# Usb_SdCard.net
KiCad netlist of a schematic drawn in Altium Designer
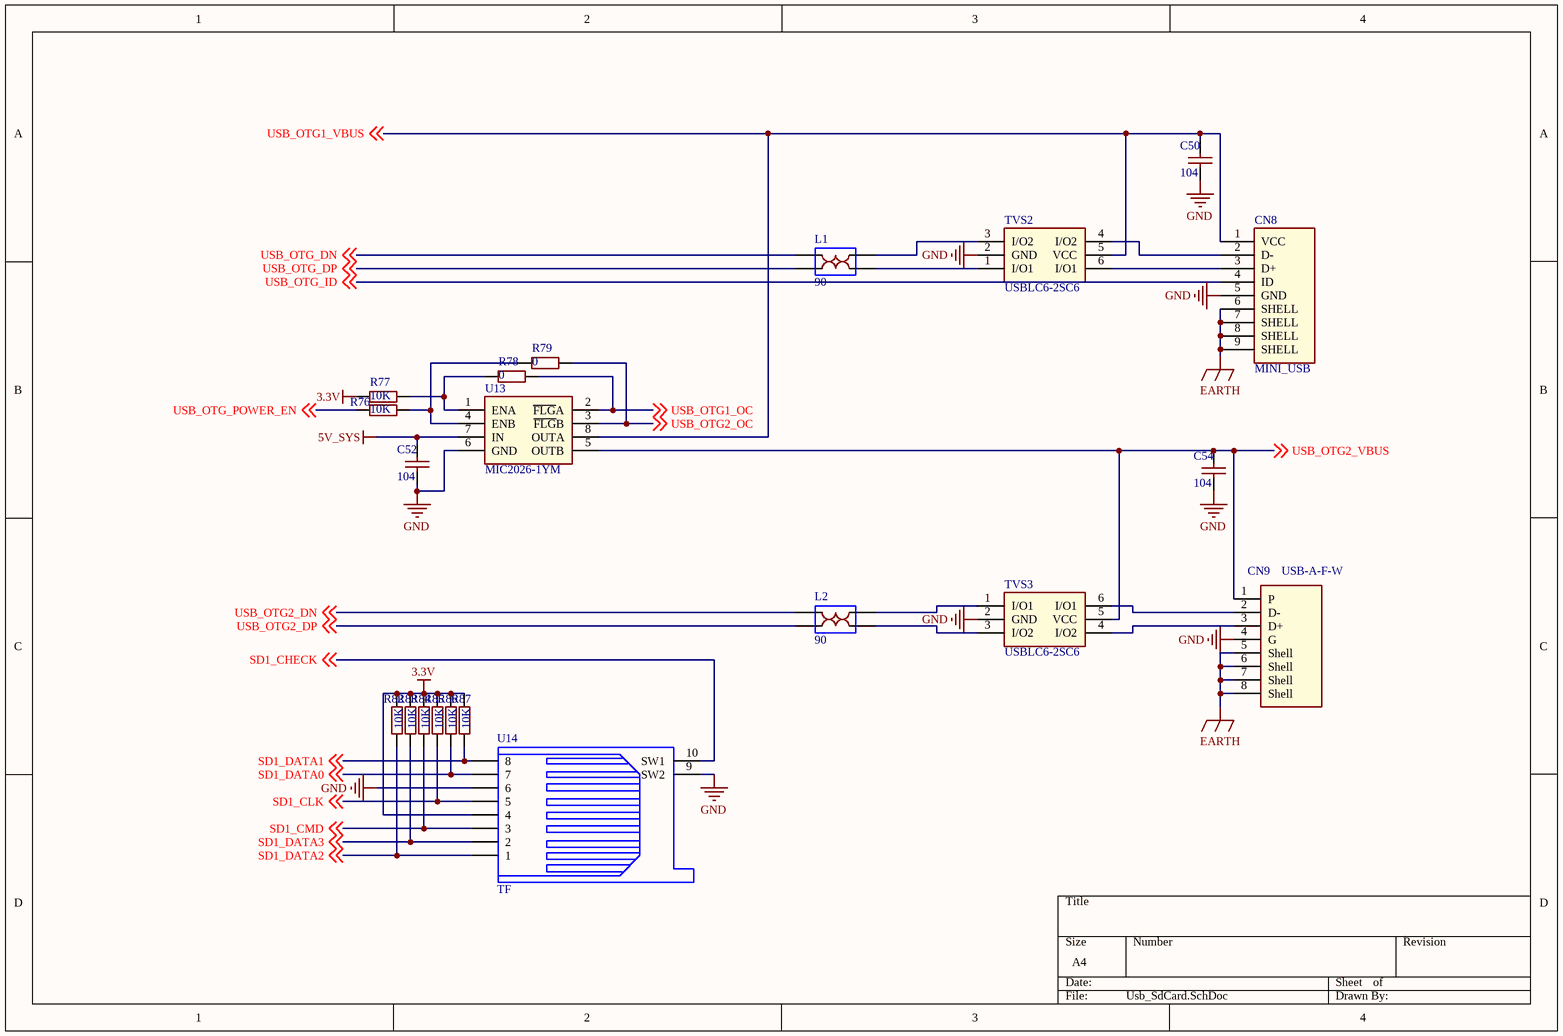
[diagram p0: Usb_SdCard.SchDoc]

(export (version "E")
  (design (tool "Eeschema 10.0.6"))
  (components
    (comp (ref "C50")
      (value "104")
      (footprint "0805SMD_Cap")
      (description "贴片电容")
      (libsource (lib "ST_GND_Sch") (part "SMD_Cap"))
    )
    (comp (ref "C52")
      (value "104")
      (footprint "0805SMD_Cap")
      (description "贴片电容")
      (libsource (lib "ST_GND_Sch") (part "SMD_Cap"))
    )
    (comp (ref "C54")
      (value "104")
      (footprint "0805SMD_Cap")
      (description "贴片电容")
      (libsource (lib "ST_GND_Sch") (part "SMD_Cap"))
    )
    (comp (ref "CN8")
      (value "MINI_USB")
      (footprint "MICRO_USB")
      (libsource (lib "ST_GND_Sch") (part "MINI_USB"))
    )
    (comp (ref "CN9")
      (value "USB-A-F-W")
      (footprint "USB-C")
      (libsource (lib "ST_GND_Sch") (part "USB-A-F-W"))
    )
    (comp (ref "L1") (value "90") (footprint "2012") (libsource (lib "") (part "共模电感_1")))
    (comp (ref "L2") (value "90") (footprint "2012") (libsource (lib "ST_GND_Sch") (part "共模电感")))
    (comp (ref "R76")
      (value "10K")
      (footprint "0805_SMD_R")
      (description "贴片电阻")
      (libsource (lib "") (part "SMD_0805_1"))
    )
    (comp (ref "R77")
      (value "10K")
      (footprint "0805_SMD_R")
      (description "贴片电阻")
      (libsource (lib "") (part "SMD_0805_1"))
    )
    (comp (ref "R78")
      (value "0")
      (footprint "0805_SMD_R")
      (description "贴片电阻")
      (libsource (lib "") (part "SMD_0805_1"))
    )
    (comp (ref "R79")
      (value "0")
      (footprint "0805_SMD_R")
      (description "贴片电阻")
      (libsource (lib "") (part "SMD_0805_1"))
    )
    (comp (ref "R82")
      (value "10K")
      (footprint "0805_SMD_R")
      (description "贴片电阻")
      (libsource (lib "ST_GND_Sch") (part "SMD_0805"))
    )
    (comp (ref "R83")
      (value "10K")
      (footprint "0805_SMD_R")
      (description "贴片电阻")
      (libsource (lib "ST_GND_Sch") (part "SMD_0805"))
    )
    (comp (ref "R84")
      (value "10K")
      (footprint "0805_SMD_R")
      (description "贴片电阻")
      (libsource (lib "ST_GND_Sch") (part "SMD_0805"))
    )
    (comp (ref "R85")
      (value "10K")
      (footprint "0805_SMD_R")
      (description "贴片电阻")
      (libsource (lib "ST_GND_Sch") (part "SMD_0805"))
    )
    (comp (ref "R86")
      (value "10K")
      (footprint "0805_SMD_R")
      (description "贴片电阻")
      (libsource (lib "ST_GND_Sch") (part "SMD_0805"))
    )
    (comp (ref "R87")
      (value "10K")
      (footprint "0805_SMD_R")
      (description "贴片电阻")
      (libsource (lib "ST_GND_Sch") (part "SMD_0805"))
    )
    (comp (ref "TVS2")
      (value "USBLC6-2SC6")
      (footprint "SOT-23-6")
      (libsource (lib "") (part "USBLC6-2SC6_1"))
    )
    (comp (ref "TVS3")
      (value "USBLC6-2SC6")
      (footprint "SOT-23-6")
      (libsource (lib "ST_GND_Sch") (part "USBLC6-2SC6"))
    )
    (comp (ref "U13")
      (value "MIC2026-1YM")
      (footprint "运放SO8")
      (libsource (lib "ST_GND_Sch") (part "MIC2026-1YM"))
    )
    (comp (ref "U14") (value "TF") (footprint "TF") (libsource (lib "ST_GND_Sch") (part "TF")))
  )
  (nets
    (net (code "1") (name "3.3V") (class "Default")
      (node (ref "R77") (pin "2") (pinfunction "2_2") (pintype "passive"))
      (node (ref "R82") (pin "2") (pinfunction "2_2") (pintype "passive"))
      (node (ref "R83") (pin "2") (pinfunction "2_2") (pintype "passive"))
      (node (ref "R84") (pin "2") (pinfunction "2_2") (pintype "passive"))
      (node (ref "R85") (pin "2") (pinfunction "2_2") (pintype "passive"))
      (node (ref "R86") (pin "2") (pinfunction "2_2") (pintype "passive"))
      (node (ref "R87") (pin "2") (pinfunction "2_2") (pintype "passive"))
      (node (ref "U14") (pin "4") (pinfunction "4_4") (pintype "passive"))
    )
    (net (code "2") (name "5V_SYS") (class "Default")
      (node (ref "C52") (pin "1") (pintype "passive"))
      (node (ref "U13") (pin "7") (pinfunction "IN_7") (pintype "passive"))
    )
    (net (code "3") (name "EARTH") (class "Default")
      (node (ref "CN8") (pin "6") (pinfunction "SHELL_6") (pintype "passive"))
      (node (ref "CN8") (pin "7") (pinfunction "SHELL_7") (pintype "passive"))
      (node (ref "CN8") (pin "8") (pinfunction "SHELL_8") (pintype "passive"))
      (node (ref "CN8") (pin "9") (pinfunction "SHELL_9") (pintype "passive"))
      (node (ref "CN9") (pin "5") (pinfunction "Shell_5") (pintype "passive"))
      (node (ref "CN9") (pin "6") (pinfunction "Shell_6") (pintype "passive"))
      (node (ref "CN9") (pin "7") (pinfunction "Shell_7") (pintype "power_in"))
      (node (ref "CN9") (pin "8") (pinfunction "Shell_8") (pintype "power_in"))
    )
    (net (code "4") (name "GND") (class "Default")
      (node (ref "C50") (pin "2") (pintype "passive"))
      (node (ref "C52") (pin "2") (pintype "passive"))
      (node (ref "C54") (pin "2") (pintype "passive"))
      (node (ref "CN8") (pin "5") (pinfunction "GND_5") (pintype "power_in"))
      (node (ref "CN9") (pin "4") (pinfunction "G_4") (pintype "passive"))
      (node (ref "TVS2") (pin "2") (pinfunction "GND_2") (pintype "passive"))
      (node (ref "TVS3") (pin "2") (pinfunction "GND_2") (pintype "passive"))
      (node (ref "U13") (pin "6") (pinfunction "GND_6") (pintype "passive"))
      (node (ref "U14") (pin "6") (pinfunction "6_6") (pintype "passive"))
      (node (ref "U14") (pin "9") (pinfunction "SW2_9") (pintype "passive"))
    )
    (net (code "5") (name "Net-(CN8-D+)") (class "Default")
      (node (ref "CN8") (pin "3") (pinfunction "D+_3") (pintype "passive"))
      (node (ref "TVS2") (pin "6") (pinfunction "I/O1_6") (pintype "passive"))
    )
    (net (code "6") (name "Net-(CN8-D-)") (class "Default")
      (node (ref "CN8") (pin "2") (pinfunction "D-_2") (pintype "passive"))
      (node (ref "TVS2") (pin "4") (pinfunction "I/O2_4") (pintype "passive"))
    )
    (net (code "7") (name "Net-(CN9-D+)") (class "Default")
      (node (ref "CN9") (pin "3") (pinfunction "D+_3") (pintype "passive"))
      (node (ref "TVS3") (pin "4") (pinfunction "I/O2_4") (pintype "passive"))
    )
    (net (code "8") (name "Net-(CN9-D-)") (class "Default")
      (node (ref "CN9") (pin "2") (pinfunction "D-_2") (pintype "passive"))
      (node (ref "TVS3") (pin "6") (pinfunction "I/O1_6") (pintype "passive"))
    )
    (net (code "9") (name "Net-(L1-Pad3)") (class "Default")
      (node (ref "L1") (pin "3") (pinfunction "3_3") (pintype "passive"))
      (node (ref "TVS2") (pin "3") (pinfunction "I/O2_3") (pintype "passive"))
    )
    (net (code "10") (name "Net-(L1-Pad4)") (class "Default")
      (node (ref "L1") (pin "4") (pinfunction "4_4") (pintype "passive"))
      (node (ref "TVS2") (pin "1") (pinfunction "I/O1_1") (pintype "passive"))
    )
    (net (code "11") (name "Net-(L2-Pad3)") (class "Default")
      (node (ref "L2") (pin "3") (pinfunction "3_3") (pintype "passive"))
      (node (ref "TVS3") (pin "3") (pinfunction "I/O2_3") (pintype "passive"))
    )
    (net (code "12") (name "Net-(L2-Pad4)") (class "Default")
      (node (ref "L2") (pin "4") (pinfunction "4_4") (pintype "passive"))
      (node (ref "TVS3") (pin "1") (pinfunction "I/O1_1") (pintype "passive"))
    )
    (net (code "13") (name "Net-(U13-ENA)") (class "Default")
      (node (ref "R77") (pin "1") (pinfunction "1_1") (pintype "passive"))
      (node (ref "R78") (pin "2") (pinfunction "2_2") (pintype "passive"))
      (node (ref "U13") (pin "1") (pinfunction "ENA_1") (pintype "passive"))
    )
    (net (code "14") (name "Net-(U13-ENB)") (class "Default")
      (node (ref "R76") (pin "1") (pinfunction "1_1") (pintype "passive"))
      (node (ref "R79") (pin "2") (pinfunction "2_2") (pintype "passive"))
      (node (ref "U13") (pin "4") (pinfunction "ENB_4") (pintype "passive"))
    )
    (net (code "15") (name "SD1_CHECK") (class "Default")
      (node (ref "U14") (pin "10") (pinfunction "SW1_10") (pintype "passive"))
    )
    (net (code "16") (name "SD1_CLK") (class "Default")
      (node (ref "R85") (pin "1") (pinfunction "1_1") (pintype "passive"))
      (node (ref "U14") (pin "5") (pinfunction "5_5") (pintype "passive"))
    )
    (net (code "17") (name "SD1_CMD") (class "Default")
      (node (ref "R84") (pin "1") (pinfunction "1_1") (pintype "passive"))
      (node (ref "U14") (pin "3") (pinfunction "3_3") (pintype "passive"))
    )
    (net (code "18") (name "SD1_DATA0") (class "Default")
      (node (ref "R86") (pin "1") (pinfunction "1_1") (pintype "passive"))
      (node (ref "U14") (pin "7") (pinfunction "7_7") (pintype "passive"))
    )
    (net (code "19") (name "SD1_DATA1") (class "Default")
      (node (ref "R87") (pin "1") (pinfunction "1_1") (pintype "passive"))
      (node (ref "U14") (pin "8") (pinfunction "8_8") (pintype "passive"))
    )
    (net (code "20") (name "SD1_DATA2") (class "Default")
      (node (ref "R82") (pin "1") (pinfunction "1_1") (pintype "passive"))
      (node (ref "U14") (pin "1") (pinfunction "1_1") (pintype "passive"))
    )
    (net (code "21") (name "SD1_DATA3") (class "Default")
      (node (ref "R83") (pin "1") (pinfunction "1_1") (pintype "passive"))
      (node (ref "U14") (pin "2") (pinfunction "2_2") (pintype "passive"))
    )
    (net (code "22") (name "USB_OTG1_OC") (class "Default")
      (node (ref "R78") (pin "1") (pinfunction "1_1") (pintype "passive"))
      (node (ref "U13") (pin "2") (pinfunction "~{FLG}A_2") (pintype "passive"))
    )
    (net (code "23") (name "USB_OTG1_VBUS") (class "Default")
      (node (ref "C50") (pin "1") (pintype "passive"))
      (node (ref "CN8") (pin "1") (pinfunction "VCC_1") (pintype "power_in"))
      (node (ref "TVS2") (pin "5") (pinfunction "VCC_5") (pintype "passive"))
      (node (ref "U13") (pin "8") (pinfunction "OUTA_8") (pintype "passive"))
    )
    (net (code "24") (name "USB_OTG2_DN") (class "Default")
      (node (ref "L2") (pin "1") (pinfunction "1_1") (pintype "passive"))
    )
    (net (code "25") (name "USB_OTG2_DP") (class "Default")
      (node (ref "L2") (pin "2") (pinfunction "2_2") (pintype "passive"))
    )
    (net (code "26") (name "USB_OTG2_OC") (class "Default")
      (node (ref "R79") (pin "1") (pinfunction "1_1") (pintype "passive"))
      (node (ref "U13") (pin "3") (pinfunction "~{FLG}B_3") (pintype "passive"))
    )
    (net (code "27") (name "USB_OTG2_VBUS") (class "Default")
      (node (ref "C54") (pin "1") (pintype "passive"))
      (node (ref "CN9") (pin "1") (pinfunction "P_1") (pintype "passive"))
      (node (ref "TVS3") (pin "5") (pinfunction "VCC_5") (pintype "passive"))
      (node (ref "U13") (pin "5") (pinfunction "OUTB_5") (pintype "passive"))
    )
    (net (code "28") (name "USB_OTG_DN") (class "Default")
      (node (ref "L1") (pin "2") (pinfunction "2_2") (pintype "passive"))
    )
    (net (code "29") (name "USB_OTG_DP") (class "Default")
      (node (ref "L1") (pin "1") (pinfunction "1_1") (pintype "passive"))
    )
    (net (code "30") (name "USB_OTG_ID") (class "Default")
      (node (ref "CN8") (pin "4") (pinfunction "ID_4") (pintype "passive"))
    )
    (net (code "31") (name "USB_OTG_POWER_EN") (class "Default")
      (node (ref "R76") (pin "2") (pinfunction "2_2") (pintype "passive"))
    )
  )
)
